# mkrd-001.net
KiCad netlist of a schematic drawn in EAGLE
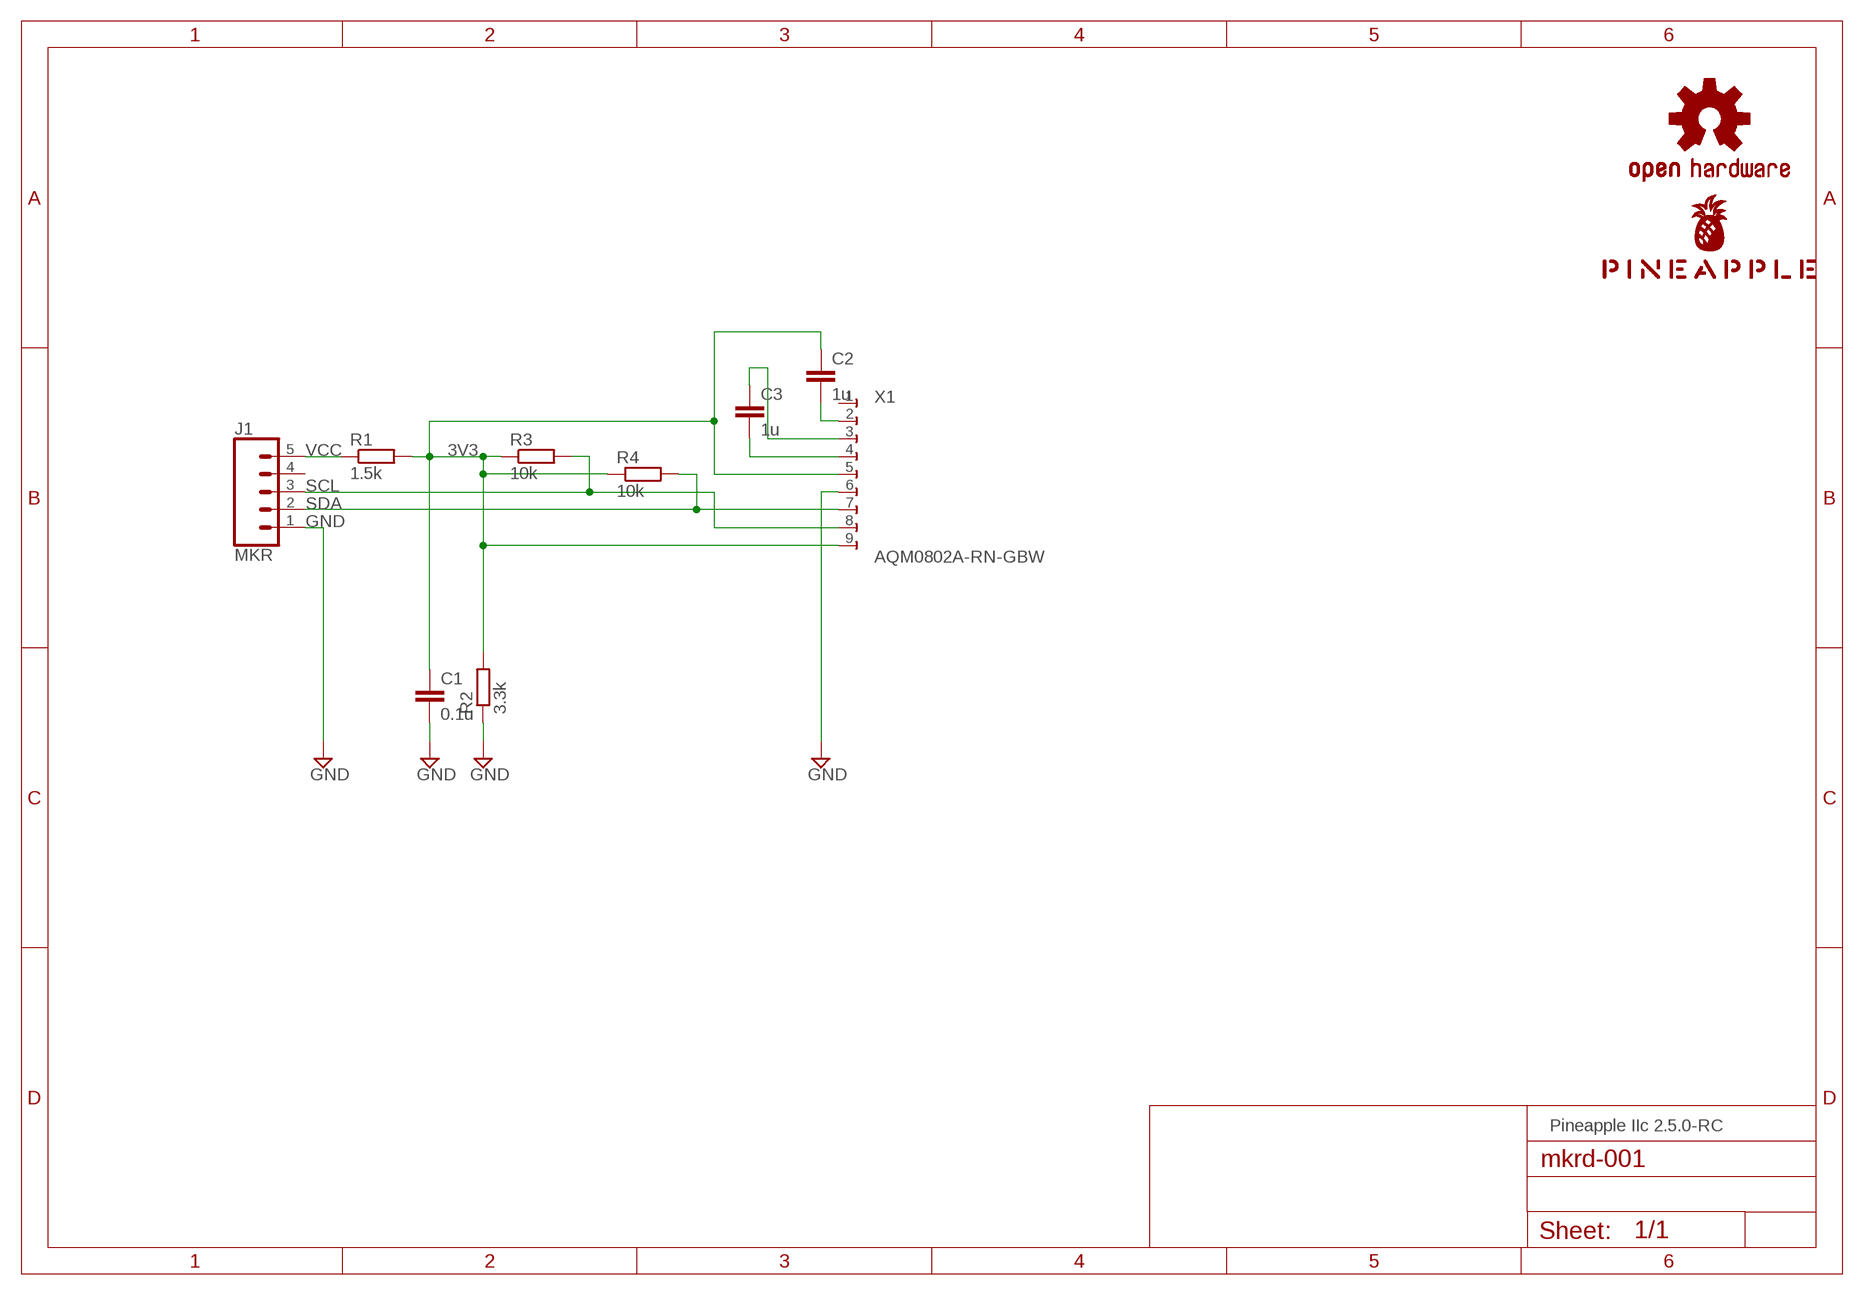
[diagram p0: schematic, sheet 1]

(export (version "E")
  (design (tool "Eeschema 10.0.6"))
  (components
    (comp (ref "C1")
      (value "0.1u")
      (footprint "eagle-import:C025-024X044")
      (libsource (lib "eagle-import") (part "C-EU025-024X044"))
    )
    (comp (ref "C2")
      (value "1u")
      (footprint "eagle-import:C025-025X050")
      (libsource (lib "eagle-import") (part "C-EU025-025X050"))
    )
    (comp (ref "C3")
      (value "1u")
      (footprint "eagle-import:C025-025X050")
      (libsource (lib "eagle-import") (part "C-EU025-025X050"))
    )
    (comp (ref "J1")
      (value "MKR")
      (footprint "eagle-import:JST-5-PTH")
      (libsource (lib "eagle-import") (part "CONN_05JST"))
    )
    (comp (ref "LOGO1")
      (value "OSHW-LOGOS-COPPER")
      (footprint "eagle-import:OSHW-LOGO-S_COPPER")
      (libsource (lib "eagle-import") (part "OSHW-LOGOS-COPPER"))
    )
    (comp (ref "R1")
      (value "1.5k")
      (footprint "eagle-import:0204_5")
      (libsource (lib "eagle-import") (part "R-EU_0204/5"))
    )
    (comp (ref "R2")
      (value "3.3k")
      (footprint "eagle-import:0204_5")
      (libsource (lib "eagle-import") (part "R-EU_0204/5"))
    )
    (comp (ref "R3")
      (value "10k")
      (footprint "eagle-import:0204_5")
      (libsource (lib "eagle-import") (part "R-EU_0204/5"))
    )
    (comp (ref "R4")
      (value "10k")
      (footprint "eagle-import:0204_5")
      (libsource (lib "eagle-import") (part "R-EU_0204/5"))
    )
    (comp (ref "U$1")
      (value "PINEAPPLE450_SILK")
      (footprint "eagle-import:PINEAPPLE450_SILK")
      (libsource (lib "eagle-import") (part "PINEAPPLE450_SILK"))
    )
    (comp (ref "X1")
      (value "AQM0802A-RN-GBW")
      (footprint "eagle-import:AQM0802A-RN-GBW-FOOTPRINT")
      (libsource (lib "eagle-import") (part "AQM0802A-RN-GBW"))
    )
  )
  (nets
    (net (code "1") (name "/3V3") (class "Default")
      (node (ref "C1") (pin "1") (pinfunction "1_1") (pintype "passive"))
      (node (ref "C2") (pin "1") (pinfunction "1_1") (pintype "passive"))
      (node (ref "R1") (pin "2") (pinfunction "2_2") (pintype "passive"))
      (node (ref "R2") (pin "2") (pinfunction "2_2") (pintype "passive"))
      (node (ref "R3") (pin "1") (pinfunction "1_1") (pintype "passive"))
      (node (ref "R4") (pin "1") (pinfunction "1_1") (pintype "passive"))
      (node (ref "X1") (pin "5") (pinfunction "5_5") (pintype "passive"))
      (node (ref "X1") (pin "9") (pinfunction "9_9") (pintype "passive"))
    )
    (net (code "2") (name "/SCL") (class "Default")
      (node (ref "J1") (pin "3") (pinfunction "3_3") (pintype "passive"))
      (node (ref "R3") (pin "2") (pinfunction "2_2") (pintype "passive"))
      (node (ref "X1") (pin "8") (pinfunction "8_8") (pintype "passive"))
    )
    (net (code "3") (name "/SDA") (class "Default")
      (node (ref "J1") (pin "2") (pinfunction "2_2") (pintype "passive"))
      (node (ref "R4") (pin "2") (pinfunction "2_2") (pintype "passive"))
      (node (ref "X1") (pin "7") (pinfunction "7_7") (pintype "passive"))
    )
    (net (code "4") (name "/VCC") (class "Default")
      (node (ref "J1") (pin "5") (pinfunction "5_5") (pintype "passive"))
      (node (ref "R1") (pin "1") (pinfunction "1_1") (pintype "passive"))
    )
    (net (code "5") (name "GND") (class "Default")
      (node (ref "C1") (pin "2") (pinfunction "2_2") (pintype "passive"))
      (node (ref "J1") (pin "1") (pinfunction "1_1") (pintype "passive"))
      (node (ref "R2") (pin "1") (pinfunction "1_1") (pintype "passive"))
      (node (ref "X1") (pin "6") (pinfunction "6_6") (pintype "passive"))
    )
    (net (code "6") (name "Net-(C2-Pad2)") (class "Default")
      (node (ref "C2") (pin "2") (pinfunction "2_2") (pintype "passive"))
      (node (ref "X1") (pin "2") (pinfunction "2_2") (pintype "passive"))
    )
    (net (code "7") (name "Net-(C3-Pad1)") (class "Default")
      (node (ref "C3") (pin "1") (pinfunction "1_1") (pintype "passive"))
      (node (ref "X1") (pin "3") (pinfunction "3_3") (pintype "passive"))
    )
    (net (code "8") (name "Net-(C3-Pad2)") (class "Default")
      (node (ref "C3") (pin "2") (pinfunction "2_2") (pintype "passive"))
      (node (ref "X1") (pin "4") (pinfunction "4_4") (pintype "passive"))
    )
    (net (code "9") (name "unconnected-(J1-Pad4)") (class "Default")
      (node (ref "J1") (pin "4") (pinfunction "4_4") (pintype "passive"))
    )
    (net (code "10") (name "unconnected-(X1-Pad1)") (class "Default")
      (node (ref "X1") (pin "1") (pinfunction "1_1") (pintype "passive"))
    )
  )
)
